# NAU7802.net
KiCad netlist of a schematic drawn in EAGLE
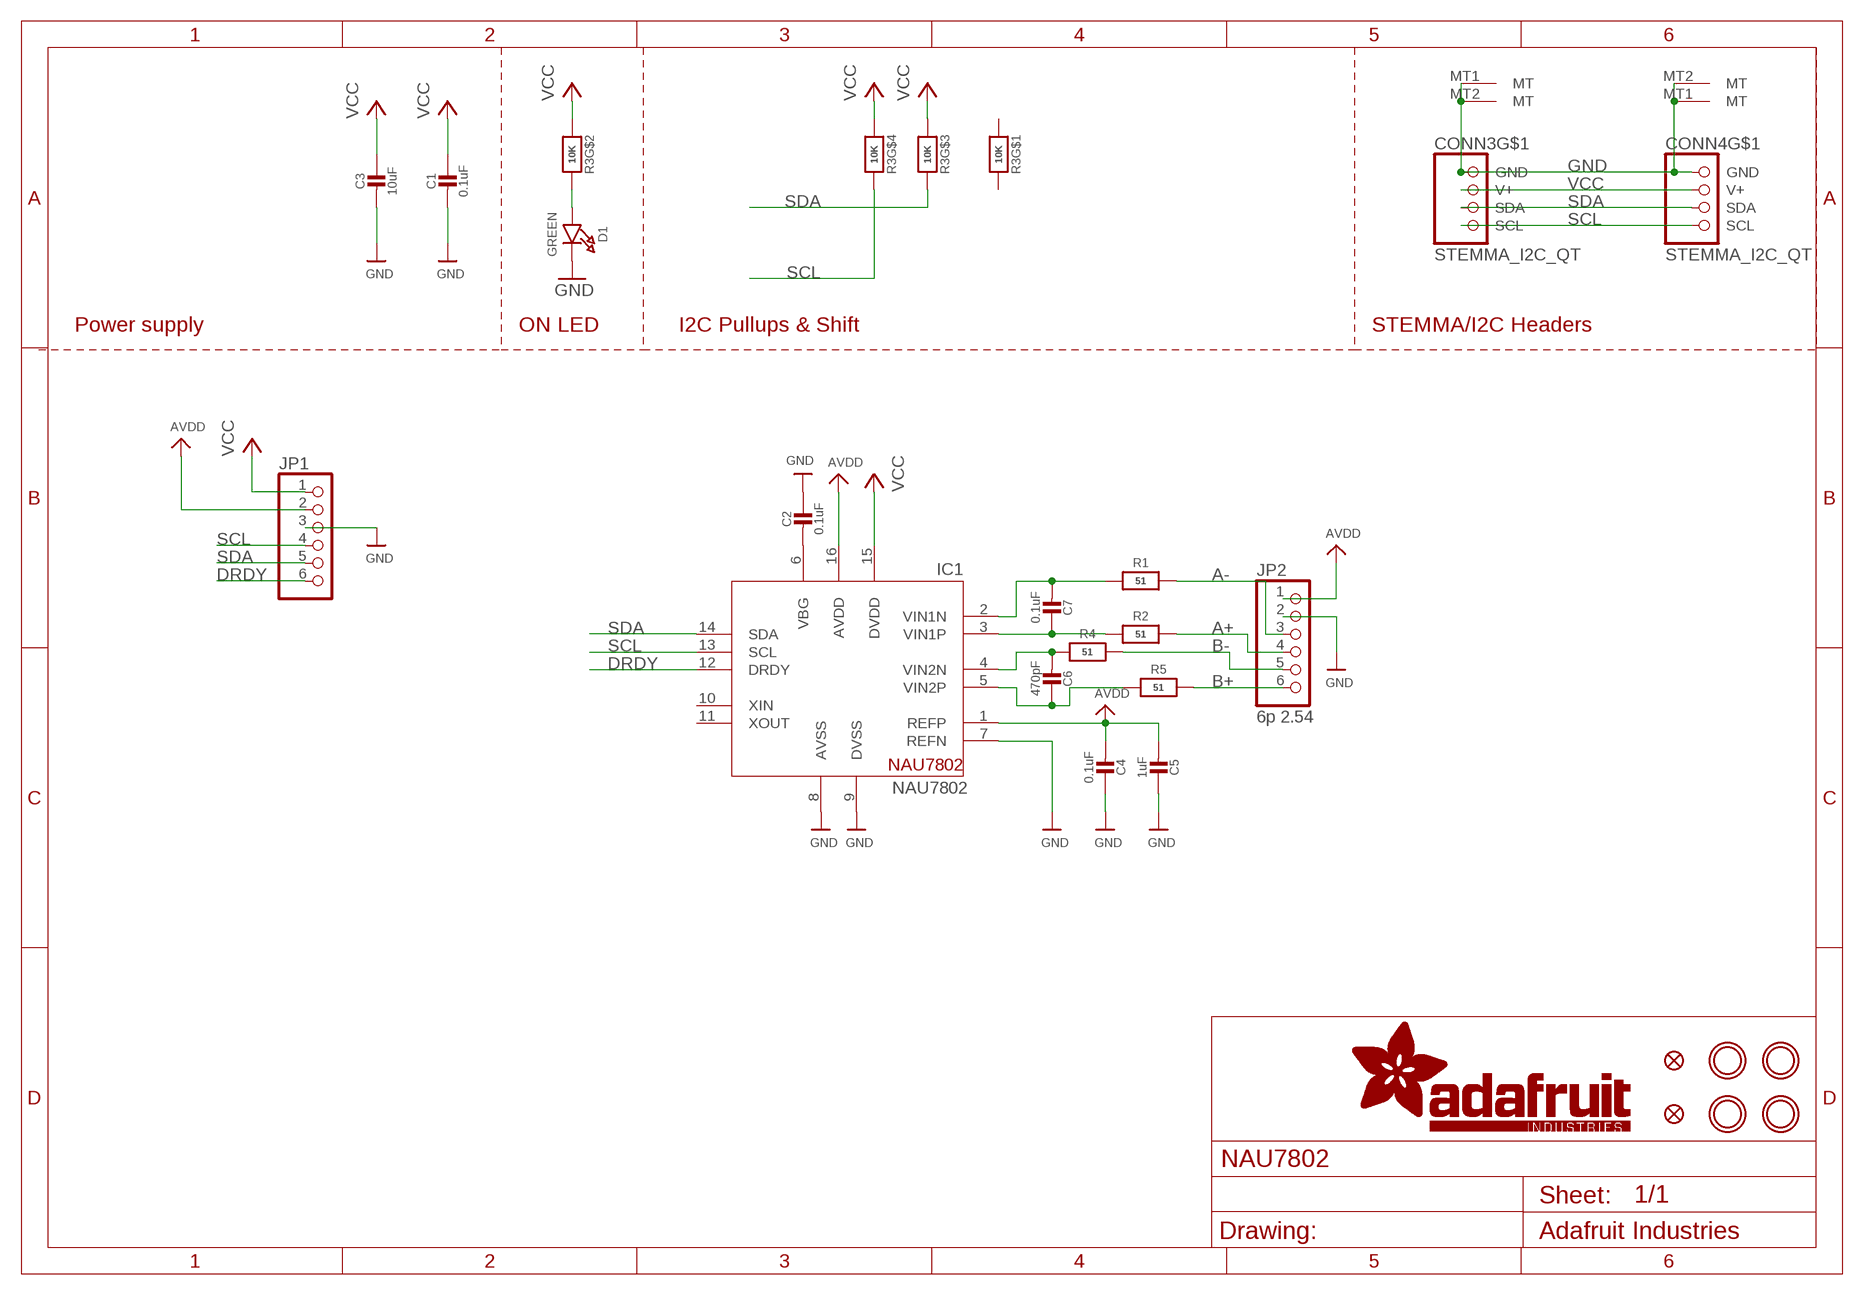
[diagram p0: schematic, sheet 1]

(export (version "E")
  (design (tool "Eeschema 10.0.6"))
  (components
    (comp (ref "C1")
      (value "0.1uF")
      (footprint "eagle-import:0603-NO")
      (libsource (lib "eagle-import") (part "CAP_CERAMIC0603_NO"))
    )
    (comp (ref "C2")
      (value "0.1uF")
      (footprint "eagle-import:0603-NO")
      (libsource (lib "eagle-import") (part "CAP_CERAMIC0603_NO"))
    )
    (comp (ref "C3")
      (value "10uF")
      (footprint "eagle-import:0805-NO")
      (libsource (lib "eagle-import") (part "CAP_CERAMIC0805-NOOUTLINE"))
    )
    (comp (ref "C4")
      (value "0.1uF")
      (footprint "eagle-import:0603-NO")
      (libsource (lib "eagle-import") (part "CAP_CERAMIC0603_NO"))
    )
    (comp (ref "C5")
      (value "1uF")
      (footprint "eagle-import:0603-NO")
      (libsource (lib "eagle-import") (part "CAP_CERAMIC0603_NO"))
    )
    (comp (ref "C6")
      (value "470pF")
      (footprint "eagle-import:0603-NO")
      (libsource (lib "eagle-import") (part "CAP_CERAMIC0603_NO"))
    )
    (comp (ref "C7")
      (value "0.1uF")
      (footprint "eagle-import:0603-NO")
      (libsource (lib "eagle-import") (part "CAP_CERAMIC0603_NO"))
    )
    (comp (ref "CONN3")
      (value "STEMMA_I2C_QT")
      (footprint "eagle-import:JST_SH4")
      (libsource (lib "eagle-import") (part "STEMMA_I2C_QT"))
    )
    (comp (ref "CONN4")
      (value "STEMMA_I2C_QT")
      (footprint "eagle-import:JST_SH4")
      (libsource (lib "eagle-import") (part "STEMMA_I2C_QT"))
    )
    (comp (ref "D1")
      (value "GREEN")
      (footprint "eagle-import:CHIPLED_0603_NOOUTLINE")
      (libsource (lib "eagle-import") (part "LED0603_NOOUTLINE"))
    )
    (comp (ref "FID3")
      (value "FIDUCIAL_0.5MM")
      (footprint "eagle-import:FIDUCIAL_0.5MM")
      (libsource (lib "eagle-import") (part "FIDUCIAL_0.5MM"))
    )
    (comp (ref "FID4")
      (value "FIDUCIAL_0.5MM")
      (footprint "eagle-import:FIDUCIAL_0.5MM")
      (libsource (lib "eagle-import") (part "FIDUCIAL_0.5MM"))
    )
    (comp (ref "IC1")
      (value "NAU7802")
      (footprint "eagle-import:SOIC16_NARROW")
      (libsource (lib "eagle-import") (part "NAU7802"))
    )
    (comp (ref "JP1")
      (value "HEADER-1X670MIL")
      (footprint "eagle-import:1X06_ROUND_70")
      (libsource (lib "eagle-import") (part "HEADER-1X670MIL"))
    )
    (comp (ref "JP2")
      (value "6p 2.54")
      (footprint "eagle-import:1X06_2.54MMTERMINAL")
      (libsource (lib "eagle-import") (part "HEADER-1X6_2.54MMTERM"))
    )
    (comp (ref "R1")
      (value "51")
      (footprint "eagle-import:0603-NO")
      (libsource (lib "eagle-import") (part "RESISTOR_0603_NOOUT"))
    )
    (comp (ref "R2")
      (value "51")
      (footprint "eagle-import:0603-NO")
      (libsource (lib "eagle-import") (part "RESISTOR_0603_NOOUT"))
    )
    (comp (ref "R3")
      (value "10K")
      (footprint "eagle-import:RESPACK_4X0603")
      (libsource (lib "eagle-import") (part "RESISTOR_4PACK"))
    )
    (comp (ref "R4")
      (value "51")
      (footprint "eagle-import:0603-NO")
      (libsource (lib "eagle-import") (part "RESISTOR_0603_NOOUT"))
    )
    (comp (ref "R5")
      (value "51")
      (footprint "eagle-import:0603-NO")
      (libsource (lib "eagle-import") (part "RESISTOR_0603_NOOUT"))
    )
    (comp (ref "U$1")
      (value "MOUNTINGHOLE2.5")
      (footprint "eagle-import:MOUNTINGHOLE_2.5_PLATED")
      (libsource (lib "eagle-import") (part "MOUNTINGHOLE2.5"))
    )
    (comp (ref "U$17")
      (value "MOUNTINGHOLE2.5")
      (footprint "eagle-import:MOUNTINGHOLE_2.5_PLATED")
      (libsource (lib "eagle-import") (part "MOUNTINGHOLE2.5"))
    )
    (comp (ref "U$19")
      (value "MOUNTINGHOLE2.5")
      (footprint "eagle-import:MOUNTINGHOLE_2.5_PLATED")
      (libsource (lib "eagle-import") (part "MOUNTINGHOLE2.5"))
    )
    (comp (ref "U$21")
      (value "MOUNTINGHOLE2.5")
      (footprint "eagle-import:MOUNTINGHOLE_2.5_PLATED")
      (libsource (lib "eagle-import") (part "MOUNTINGHOLE2.5"))
    )
  )
  (nets
    (net (code "1") (name "/A+") (class "Default")
      (node (ref "JP2") (pin "4") (pinfunction "4_4") (pintype "passive"))
      (node (ref "R2") (pin "2") (pinfunction "2_2") (pintype "passive"))
    )
    (net (code "2") (name "/A-") (class "Default")
      (node (ref "JP2") (pin "3") (pinfunction "3_3") (pintype "passive"))
      (node (ref "R1") (pin "2") (pinfunction "2_2") (pintype "passive"))
    )
    (net (code "3") (name "/B+") (class "Default")
      (node (ref "JP2") (pin "6") (pinfunction "6_6") (pintype "passive"))
      (node (ref "R5") (pin "2") (pinfunction "2_2") (pintype "passive"))
    )
    (net (code "4") (name "/B-") (class "Default")
      (node (ref "JP2") (pin "5") (pinfunction "5_5") (pintype "passive"))
      (node (ref "R4") (pin "2") (pinfunction "2_2") (pintype "passive"))
    )
    (net (code "5") (name "/DRDY") (class "Default")
      (node (ref "IC1") (pin "12") (pinfunction "DRDY_12") (pintype "output"))
      (node (ref "JP1") (pin "6") (pinfunction "6_6") (pintype "passive"))
    )
    (net (code "6") (name "/SCL") (class "Default")
      (node (ref "CONN3") (pin "4") (pinfunction "SCL_4") (pintype "passive"))
      (node (ref "CONN4") (pin "4") (pinfunction "SCL_4") (pintype "passive"))
      (node (ref "IC1") (pin "13") (pinfunction "SCL_13") (pintype "bidirectional"))
      (node (ref "JP1") (pin "4") (pinfunction "4_4") (pintype "passive"))
      (node (ref "R3") (pin "5") (pinfunction "2_5") (pintype "passive"))
    )
    (net (code "7") (name "/SDA") (class "Default")
      (node (ref "CONN3") (pin "3") (pinfunction "SDA_3") (pintype "passive"))
      (node (ref "CONN4") (pin "3") (pinfunction "SDA_3") (pintype "passive"))
      (node (ref "IC1") (pin "14") (pinfunction "SDA_14") (pintype "bidirectional"))
      (node (ref "JP1") (pin "5") (pinfunction "5_5") (pintype "passive"))
      (node (ref "R3") (pin "6") (pinfunction "2_6") (pintype "passive"))
    )
    (net (code "8") (name "AVDD") (class "Default")
      (node (ref "C4") (pin "2") (pinfunction "2_2") (pintype "passive"))
      (node (ref "C5") (pin "2") (pinfunction "2_2") (pintype "passive"))
      (node (ref "IC1") (pin "1") (pinfunction "REFP_1") (pintype "input"))
      (node (ref "IC1") (pin "16") (pinfunction "AVDD_16") (pintype "power_in"))
      (node (ref "JP1") (pin "2") (pinfunction "2_2") (pintype "passive"))
      (node (ref "JP2") (pin "1") (pinfunction "1_1") (pintype "passive"))
    )
    (net (code "9") (name "GND") (class "Default")
      (node (ref "C1") (pin "2") (pinfunction "2_2") (pintype "passive"))
      (node (ref "C2") (pin "1") (pinfunction "1_1") (pintype "passive"))
      (node (ref "C3") (pin "2") (pinfunction "2_2") (pintype "passive"))
      (node (ref "C4") (pin "1") (pinfunction "1_1") (pintype "passive"))
      (node (ref "C5") (pin "1") (pinfunction "1_1") (pintype "passive"))
      (node (ref "CONN3") (pin "1") (pinfunction "GND_1") (pintype "passive"))
      (node (ref "CONN3") (pin "MT1") (pinfunction "MT_MT1") (pintype "bidirectional"))
      (node (ref "CONN3") (pin "MT2") (pinfunction "MT_MT2") (pintype "bidirectional"))
      (node (ref "CONN4") (pin "1") (pinfunction "GND_1") (pintype "passive"))
      (node (ref "CONN4") (pin "MT1") (pinfunction "MT_MT1") (pintype "bidirectional"))
      (node (ref "CONN4") (pin "MT2") (pinfunction "MT_MT2") (pintype "bidirectional"))
      (node (ref "D1") (pin "C") (pinfunction "C_C") (pintype "passive"))
      (node (ref "IC1") (pin "7") (pinfunction "REFN_7") (pintype "input"))
      (node (ref "IC1") (pin "8") (pinfunction "AVSS_8") (pintype "power_in"))
      (node (ref "IC1") (pin "9") (pinfunction "DVSS_9") (pintype "power_in"))
      (node (ref "JP1") (pin "3") (pinfunction "3_3") (pintype "passive"))
      (node (ref "JP2") (pin "2") (pinfunction "2_2") (pintype "passive"))
    )
    (net (code "10") (name "Net-(IC1-VBG)") (class "Default")
      (node (ref "C2") (pin "2") (pinfunction "2_2") (pintype "passive"))
      (node (ref "IC1") (pin "6") (pinfunction "VBG_6") (pintype "power_in"))
    )
    (net (code "11") (name "Net-(IC1-VIN1N)") (class "Default")
      (node (ref "C7") (pin "2") (pinfunction "2_2") (pintype "passive"))
      (node (ref "IC1") (pin "2") (pinfunction "VIN1N_2") (pintype "input"))
      (node (ref "R1") (pin "1") (pinfunction "1_1") (pintype "passive"))
    )
    (net (code "12") (name "Net-(IC1-VIN1P)") (class "Default")
      (node (ref "C7") (pin "1") (pinfunction "1_1") (pintype "passive"))
      (node (ref "IC1") (pin "3") (pinfunction "VIN1P_3") (pintype "input"))
      (node (ref "R2") (pin "1") (pinfunction "1_1") (pintype "passive"))
    )
    (net (code "13") (name "Net-(IC1-VIN2N)") (class "Default")
      (node (ref "C6") (pin "2") (pinfunction "2_2") (pintype "passive"))
      (node (ref "IC1") (pin "4") (pinfunction "VIN2N_4") (pintype "input"))
      (node (ref "R4") (pin "1") (pinfunction "1_1") (pintype "passive"))
    )
    (net (code "14") (name "Net-(IC1-VIN2P)") (class "Default")
      (node (ref "C6") (pin "1") (pinfunction "1_1") (pintype "passive"))
      (node (ref "IC1") (pin "5") (pinfunction "VIN2P_5") (pintype "input"))
      (node (ref "R5") (pin "1") (pinfunction "1_1") (pintype "passive"))
    )
    (net (code "15") (name "Net-(R3B-2)") (class "Default")
      (node (ref "D1") (pin "A") (pinfunction "A_A") (pintype "passive"))
      (node (ref "R3") (pin "7") (pinfunction "2_7") (pintype "passive"))
    )
    (net (code "16") (name "VCC") (class "Default")
      (node (ref "C1") (pin "1") (pinfunction "1_1") (pintype "passive"))
      (node (ref "C3") (pin "1") (pinfunction "1_1") (pintype "passive"))
      (node (ref "CONN3") (pin "2") (pinfunction "V+_2") (pintype "passive"))
      (node (ref "CONN4") (pin "2") (pinfunction "V+_2") (pintype "passive"))
      (node (ref "IC1") (pin "15") (pinfunction "DVDD_15") (pintype "power_in"))
      (node (ref "JP1") (pin "1") (pinfunction "1_1") (pintype "passive"))
      (node (ref "R3") (pin "2") (pinfunction "1_2") (pintype "passive"))
      (node (ref "R3") (pin "3") (pinfunction "1_3") (pintype "passive"))
      (node (ref "R3") (pin "4") (pinfunction "1_4") (pintype "passive"))
    )
    (net (code "17") (name "unconnected-(IC1-XIN-Pad10)") (class "Default")
      (node (ref "IC1") (pin "10") (pinfunction "XIN_10") (pintype "passive"))
    )
    (net (code "18") (name "unconnected-(IC1-XOUT-Pad11)") (class "Default")
      (node (ref "IC1") (pin "11") (pinfunction "XOUT_11") (pintype "passive"))
    )
    (net (code "19") (name "unconnected-(R3-Pad1)") (class "Default")
      (node (ref "R3") (pin "1") (pinfunction "1_1") (pintype "passive"))
    )
    (net (code "20") (name "unconnected-(R3A-2-Pad8)") (class "Default")
      (node (ref "R3") (pin "8") (pinfunction "2_8") (pintype "passive"))
    )
  )
)
